# Domino_Qi.net
KiCad netlist of a schematic drawn in EAGLE
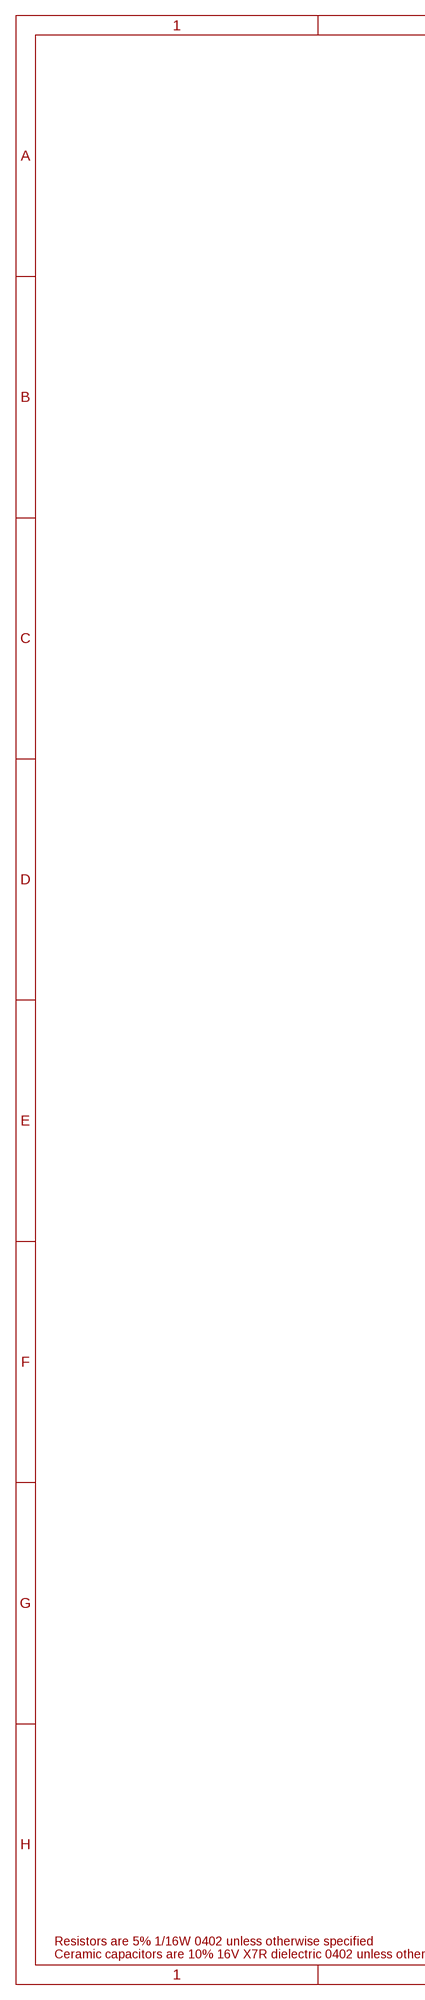
[diagram p0: schematic, sheet 1, part 1 of 2]
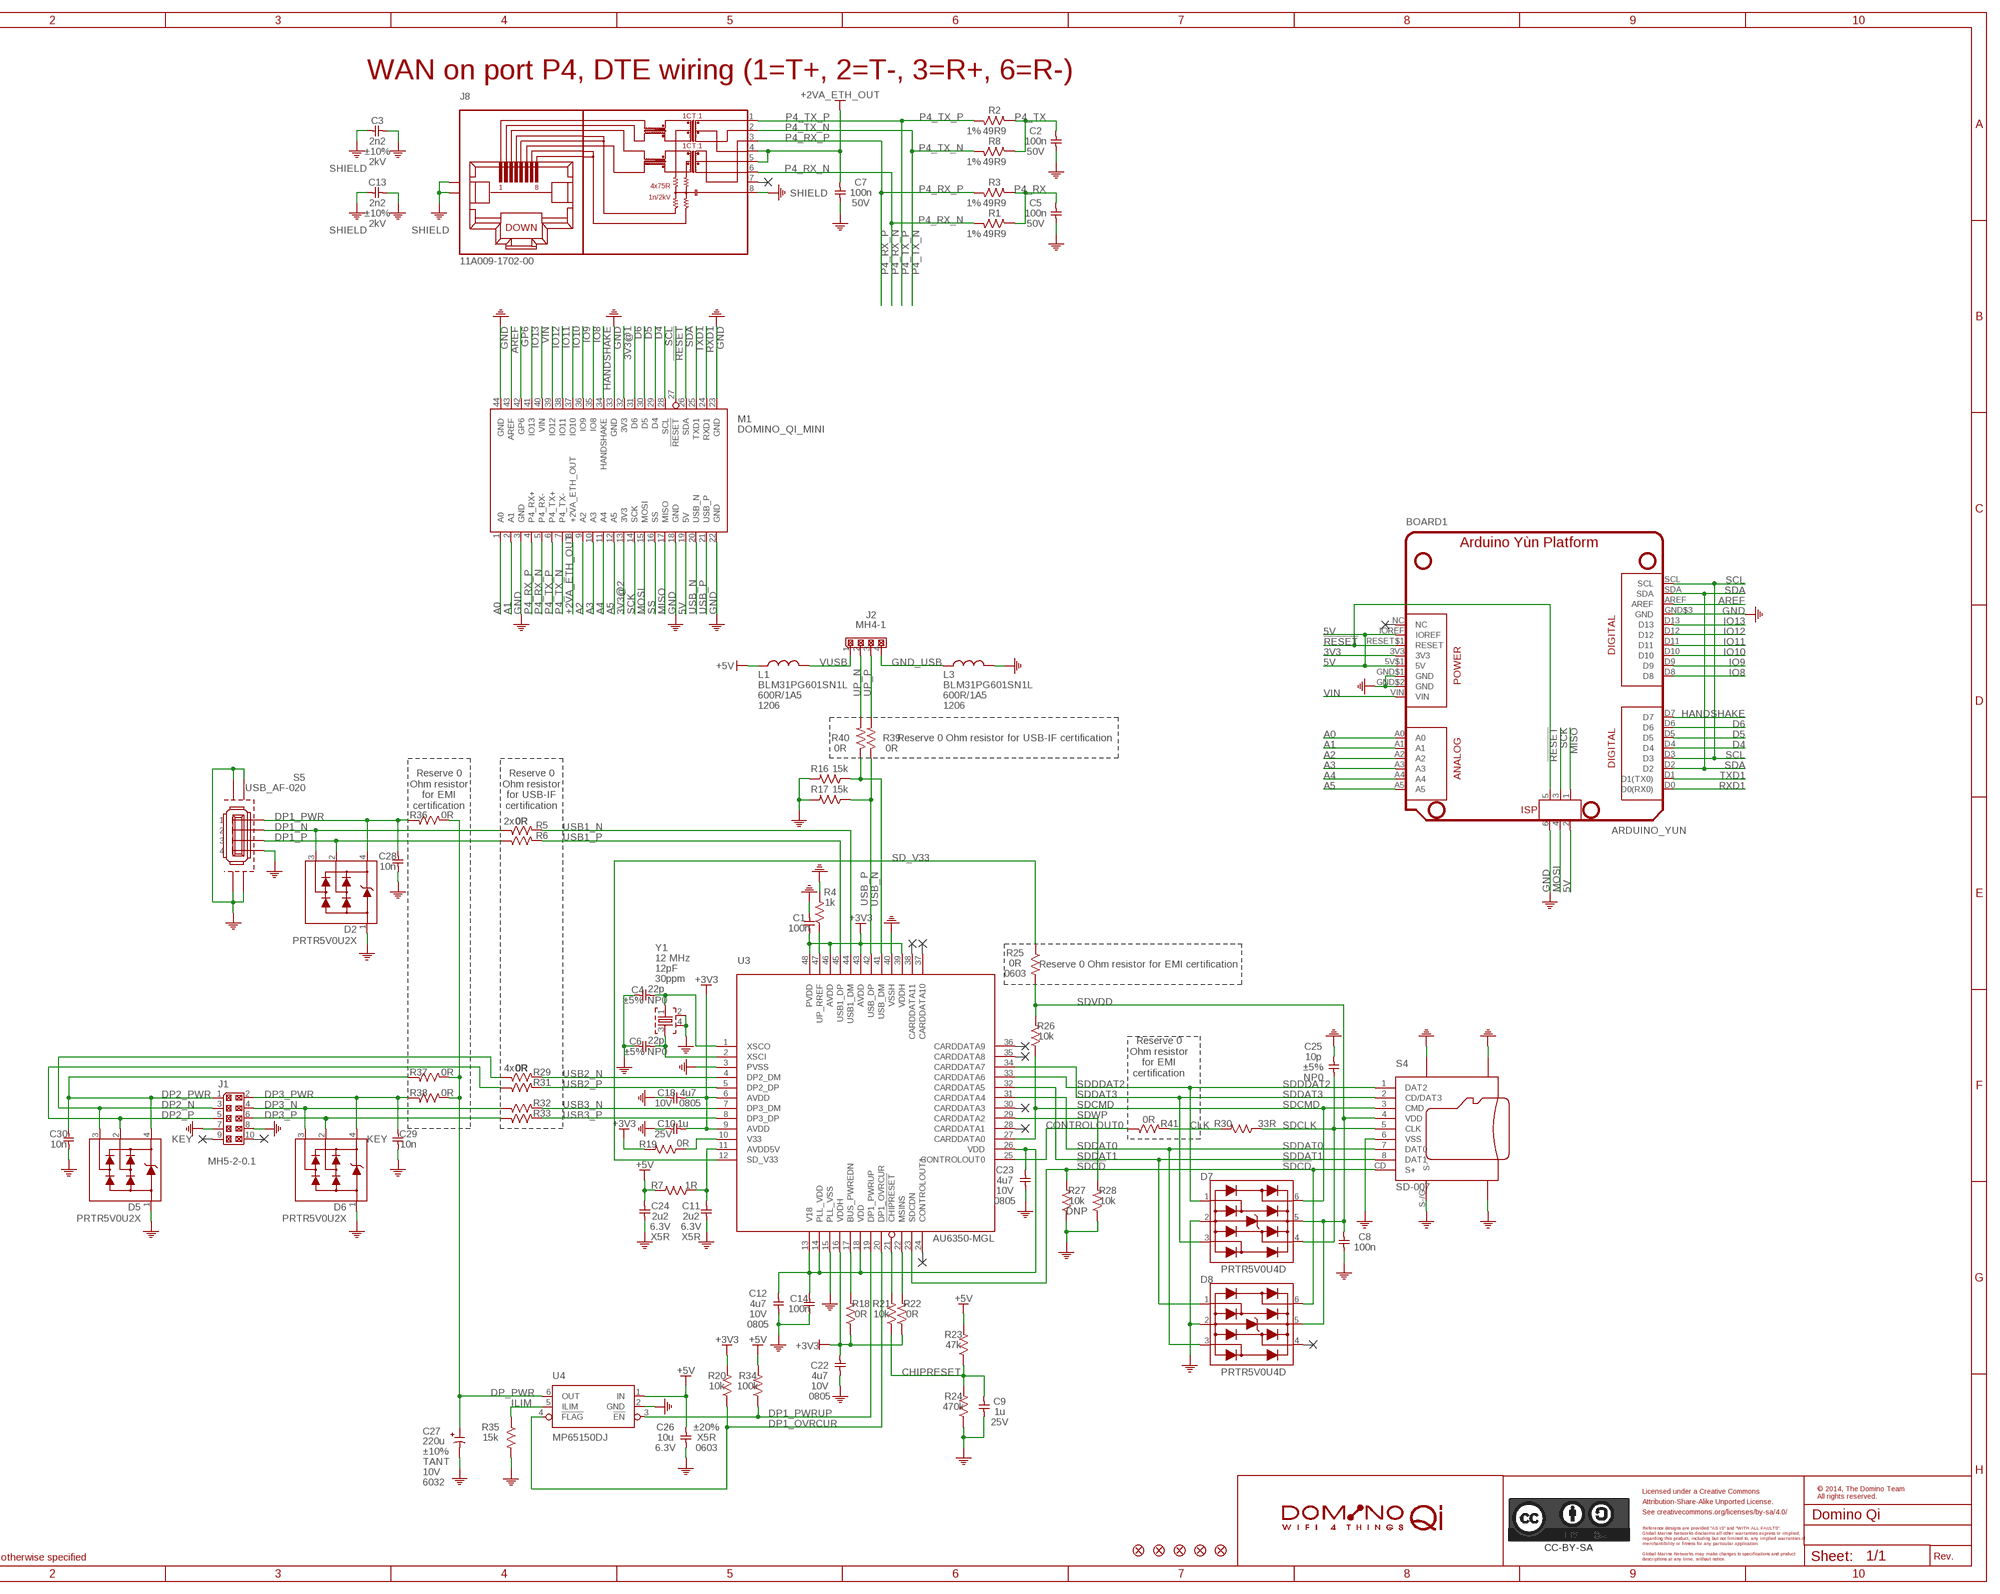
[diagram p1: schematic, sheet 1, part 2 of 2]

(export (version "E")
  (design (tool "Eeschema 10.0.6"))
  (components
    (comp (ref "BOARD1")
      (value "ARDUINO_YUN")
      (footprint "eagle-import:ARDUINO-YUN-PLATFORM")
      (libsource (lib "eagle-import") (part "ARDUINO_YUN"))
    )
    (comp (ref "C1")
      (value "100n")
      (footprint "eagle-import:C0402")
      (fields (field (name "PARTNO") "C0402_100n_X7R_10%_CER_50V"))
      (libsource (lib "eagle-import") (part "CAP_0402"))
    )
    (comp (ref "C2")
      (value "100n")
      (footprint "eagle-import:C0402")
      (fields (field (name "PARTNO") "C0402_100n_X7R_10%_CER_50V") (field (name "VOLT") "50V"))
      (libsource (lib "eagle-import") (part "CAP_0402"))
    )
    (comp (ref "C3")
      (value "2n2")
      (footprint "eagle-import:C1206")
      (fields
        (field (name "PARTNO") "C1210_2n2_X7R_10%_CER_2kV")
        (field (name "TOL") "±10%")
        (field (name "VOLT") "2kV")
      )
      (libsource (lib "eagle-import") (part "CAP_1206"))
    )
    (comp (ref "C4")
      (value "22p")
      (footprint "eagle-import:C0402")
      (fields
        (field (name "PARTNO") "C0402_22p_NP0_5%_CER_50V")
        (field (name "TC") "NP0")
        (field (name "TOL") "±5%")
      )
      (libsource (lib "eagle-import") (part "CAP_0402"))
    )
    (comp (ref "C5")
      (value "100n")
      (footprint "eagle-import:C0402")
      (fields (field (name "PARTNO") "C0402_100n_X7R_10%_CER_50V") (field (name "VOLT") "50V"))
      (libsource (lib "eagle-import") (part "CAP_0402"))
    )
    (comp (ref "C6")
      (value "22p")
      (footprint "eagle-import:C0402")
      (fields
        (field (name "PARTNO") "C0402_22p_NP0_5%_CER_50V")
        (field (name "TC") "NP0")
        (field (name "TOL") "±5%")
      )
      (libsource (lib "eagle-import") (part "CAP_0402"))
    )
    (comp (ref "C7")
      (value "100n")
      (footprint "eagle-import:C0402")
      (fields (field (name "PARTNO") "C0402_100n_X7R_10%_CER_50V") (field (name "VOLT") "50V"))
      (libsource (lib "eagle-import") (part "CAP_0402"))
    )
    (comp (ref "C8")
      (value "100n")
      (footprint "eagle-import:C0402")
      (fields (field (name "PARTNO") "C0402_100n_X7R_10%_CER_50V"))
      (libsource (lib "eagle-import") (part "CAP_0402"))
    )
    (comp (ref "C9")
      (value "1u")
      (footprint "eagle-import:C0402")
      (fields (field (name "PARTNO") "C0402_1u_X7R_10%_CER_25V") (field (name "VOLT") "25V"))
      (libsource (lib "eagle-import") (part "CAP_0402"))
    )
    (comp (ref "C10")
      (value "1u")
      (footprint "eagle-import:C0402")
      (fields (field (name "PARTNO") "C0402_1u_X7R_10%_CER_25V") (field (name "VOLT") "25V"))
      (libsource (lib "eagle-import") (part "CAP_0402"))
    )
    (comp (ref "C11")
      (value "2u2")
      (footprint "eagle-import:C0402")
      (fields
        (field (name "PARTNO") "C0402_2u2_X5R_10%_CER_6V3")
        (field (name "TC") "X5R")
        (field (name "VOLT") "6.3V")
      )
      (libsource (lib "eagle-import") (part "CAP_0402"))
    )
    (comp (ref "C12")
      (value "4u7")
      (footprint "eagle-import:C0805")
      (fields
        (field (name "SIZE") "0805")
        (field (name "PARTNO") "C0805_4u7_X7R_10%_CER_6V3")
        (field (name "VOLT") "10V")
      )
      (libsource (lib "eagle-import") (part "CAP_0805"))
    )
    (comp (ref "C13")
      (value "2n2")
      (footprint "eagle-import:C1206")
      (fields
        (field (name "PARTNO") "C1210_2n2_X7R_10%_CER_2kV")
        (field (name "TOL") "±10%")
        (field (name "VOLT") "2kV")
      )
      (libsource (lib "eagle-import") (part "CAP_1206"))
    )
    (comp (ref "C14")
      (value "100n")
      (footprint "eagle-import:C0402")
      (fields (field (name "PARTNO") "C0402_100n_X7R_10%_CER_50V"))
      (libsource (lib "eagle-import") (part "CAP_0402"))
    )
    (comp (ref "C18")
      (value "4u7")
      (footprint "eagle-import:C0805")
      (fields
        (field (name "SIZE") "0805")
        (field (name "PARTNO") "C0805_4u7_X7R_10%_CER_6V3")
        (field (name "VOLT") "10V")
      )
      (libsource (lib "eagle-import") (part "CAP_0805"))
    )
    (comp (ref "C22")
      (value "4u7")
      (footprint "eagle-import:C0805")
      (fields
        (field (name "SIZE") "0805")
        (field (name "PARTNO") "C0805_4u7_X7R_10%_CER_6V3")
        (field (name "VOLT") "10V")
      )
      (libsource (lib "eagle-import") (part "CAP_0805"))
    )
    (comp (ref "C23")
      (value "4u7")
      (footprint "eagle-import:C0805")
      (fields
        (field (name "SIZE") "0805")
        (field (name "PARTNO") "C0805_4u7_X7R_10%_CER_6V3")
        (field (name "VOLT") "10V")
      )
      (libsource (lib "eagle-import") (part "CAP_0805"))
    )
    (comp (ref "C24")
      (value "2u2")
      (footprint "eagle-import:C0402")
      (fields
        (field (name "PARTNO") "C0402_2u2_X5R_10%_CER_6V3")
        (field (name "TC") "X5R")
        (field (name "VOLT") "6.3V")
      )
      (libsource (lib "eagle-import") (part "CAP_0402"))
    )
    (comp (ref "C25")
      (value "10p")
      (footprint "eagle-import:C0402")
      (fields
        (field (name "PARTNO") "C0402_10p_NP0_5%_CER_50V")
        (field (name "TC") "NP0")
        (field (name "TOL") "±5%")
      )
      (libsource (lib "eagle-import") (part "CAP_0402"))
    )
    (comp (ref "C26")
      (value "10u")
      (footprint "eagle-import:C0603")
      (fields
        (field (name "SIZE") "0603")
        (field (name "PARTNO") "C0603_10u_X5R_20%_CER_6V3")
        (field (name "TC") "X5R")
        (field (name "TOL") "±20%")
        (field (name "VOLT") "6.3V")
      )
      (libsource (lib "eagle-import") (part "CAP_0603"))
    )
    (comp (ref "C27")
      (value "220u")
      (footprint "eagle-import:C_6032-25")
      (fields
        (field (name "SIZE") "6032")
        (field (name "TYPE") "TANT")
        (field (name "PARTNO") "CPOLC-6032_220u_20%_TANT_10V")
        (field (name "TOL") "±10%")
        (field (name "VOLT") "10V")
      )
      (libsource (lib "eagle-import") (part "CPOL_?C/6032-25"))
    )
    (comp (ref "C28")
      (value "10n")
      (footprint "eagle-import:C0402")
      (fields (field (name "PARTNO") "C0402_10n_X7R_10%_CER_50V"))
      (libsource (lib "eagle-import") (part "CAP_0402"))
    )
    (comp (ref "C29")
      (value "10n")
      (footprint "eagle-import:C0402")
      (fields (field (name "PARTNO") "C0402_10n_X7R_10%_CER_50V"))
      (libsource (lib "eagle-import") (part "CAP_0402"))
    )
    (comp (ref "C30")
      (value "10n")
      (footprint "eagle-import:C0402")
      (fields (field (name "PARTNO") "C0402_10n_X7R_10%_CER_50V"))
      (libsource (lib "eagle-import") (part "CAP_0402"))
    )
    (comp (ref "D2")
      (value "PRTR5V0U2X")
      (footprint "eagle-import:SOT143B")
      (libsource (lib "eagle-import") (part "PRTR5V0U2X"))
    )
    (comp (ref "D5")
      (value "PRTR5V0U2X")
      (footprint "eagle-import:SOT143B")
      (libsource (lib "eagle-import") (part "PRTR5V0U2X"))
    )
    (comp (ref "D6")
      (value "PRTR5V0U2X")
      (footprint "eagle-import:SOT143B")
      (libsource (lib "eagle-import") (part "PRTR5V0U2X"))
    )
    (comp (ref "D7")
      (value "PRTR5V0U4D")
      (footprint "eagle-import:SOT23-6")
      (libsource (lib "eagle-import") (part "PRTR5V0U4D"))
    )
    (comp (ref "D8")
      (value "PRTR5V0U4D")
      (footprint "eagle-import:SOT23-6")
      (libsource (lib "eagle-import") (part "PRTR5V0U4D"))
    )
    (comp (ref "F1")
      (value "FIDUCIAL")
      (footprint "eagle-import:FIDUCIAL")
      (libsource (lib "eagle-import") (part "FIDUCIAL"))
    )
    (comp (ref "F2")
      (value "FIDUCIAL")
      (footprint "eagle-import:FIDUCIAL")
      (libsource (lib "eagle-import") (part "FIDUCIAL"))
    )
    (comp (ref "F4")
      (value "FIDUCIAL")
      (footprint "eagle-import:FIDUCIAL")
      (libsource (lib "eagle-import") (part "FIDUCIAL"))
    )
    (comp (ref "F5")
      (value "FIDUCIAL")
      (footprint "eagle-import:FIDUCIAL")
      (libsource (lib "eagle-import") (part "FIDUCIAL"))
    )
    (comp (ref "F6")
      (value "FIDUCIAL")
      (footprint "eagle-import:FIDUCIAL")
      (libsource (lib "eagle-import") (part "FIDUCIAL"))
    )
    (comp (ref "J1")
      (value "MH5-2-0.1")
      (footprint "eagle-import:MH05-2-0.1")
      (libsource (lib "eagle-import") (part "MH5-2"))
    )
    (comp (ref "J2")
      (value "MH4-1")
      (footprint "eagle-import:MH4-1-0.1")
      (fields (field (name "PARTNO") "MH4-1-0.1"))
      (libsource (lib "eagle-import") (part "MH4-1"))
    )
    (comp (ref "J8")
      (value "11A009-1702-00")
      (footprint "eagle-import:11A009-1702-00")
      (libsource (lib "eagle-import") (part "11A009-1702-00"))
    )
    (comp (ref "L1")
      (value "BLM31PG601SN1L")
      (footprint "eagle-import:FB1206")
      (fields (field (name "SIZE") "1206") (field (name "OPT") "600R/1A5"))
      (libsource (lib "eagle-import") (part "FB_1206"))
    )
    (comp (ref "L3")
      (value "BLM31PG601SN1L")
      (footprint "eagle-import:FB1206")
      (fields (field (name "SIZE") "1206") (field (name "OPT") "600R/1A5"))
      (libsource (lib "eagle-import") (part "FB_1206"))
    )
    (comp (ref "M1")
      (value "DOMINO_QI_MINI")
      (footprint "eagle-import:DOMINO_QI_MINI")
      (libsource (lib "eagle-import") (part "DOMINO_QI_MINI"))
    )
    (comp (ref "R1")
      (value "49R9")
      (footprint "eagle-import:R0402")
      (fields (field (name "PARTNO") "R0402_49R9_1%_62.5mW") (field (name "TOL") "1%"))
      (libsource (lib "eagle-import") (part "RES_0402"))
    )
    (comp (ref "R2")
      (value "49R9")
      (footprint "eagle-import:R0402")
      (fields (field (name "PARTNO") "R0402_49R9_1%_62.5mW") (field (name "TOL") "1%"))
      (libsource (lib "eagle-import") (part "RES_0402"))
    )
    (comp (ref "R3")
      (value "49R9")
      (footprint "eagle-import:R0402")
      (fields (field (name "PARTNO") "R0402_49R9_1%_62.5mW") (field (name "TOL") "1%"))
      (libsource (lib "eagle-import") (part "RES_0402"))
    )
    (comp (ref "R4")
      (value "1k")
      (footprint "eagle-import:R0402")
      (fields (field (name "PARTNO") "R0402_1k_5%_62.5mW"))
      (libsource (lib "eagle-import") (part "RES_0402"))
    )
    (comp (ref "R5")
      (value "0R")
      (footprint "eagle-import:R0402")
      (fields (field (name "PARTNO") "R0402_0R_5%_62.5mW"))
      (libsource (lib "eagle-import") (part "RES_0402"))
    )
    (comp (ref "R6")
      (value "0R")
      (footprint "eagle-import:R0402")
      (fields (field (name "PARTNO") "R0402_0R_5%_62.5mW"))
      (libsource (lib "eagle-import") (part "RES_0402"))
    )
    (comp (ref "R7")
      (value "1R")
      (footprint "eagle-import:R0402")
      (fields (field (name "PARTNO") "R0402_1R_5%_62.5mW"))
      (libsource (lib "eagle-import") (part "RES_0402"))
    )
    (comp (ref "R8")
      (value "49R9")
      (footprint "eagle-import:R0402")
      (fields (field (name "PARTNO") "R0402_49R9_1%_62.5mW") (field (name "TOL") "1%"))
      (libsource (lib "eagle-import") (part "RES_0402"))
    )
    (comp (ref "R16")
      (value "15k")
      (footprint "eagle-import:R0402")
      (fields (field (name "PARTNO") "R0402_15k_5%_62.5mW"))
      (libsource (lib "eagle-import") (part "RES_0402"))
    )
    (comp (ref "R17")
      (value "15k")
      (footprint "eagle-import:R0402")
      (fields (field (name "PARTNO") "R0402_15k_5%_62.5mW"))
      (libsource (lib "eagle-import") (part "RES_0402"))
    )
    (comp (ref "R18")
      (value "0R")
      (footprint "eagle-import:R0402")
      (fields (field (name "PARTNO") "R0402_0R_5%_62.5mW"))
      (libsource (lib "eagle-import") (part "RES_0402"))
    )
    (comp (ref "R19")
      (value "0R")
      (footprint "eagle-import:R0402")
      (fields (field (name "PARTNO") "R0402_0R_5%_62.5mW"))
      (libsource (lib "eagle-import") (part "RES_0402"))
    )
    (comp (ref "R20")
      (value "10k")
      (footprint "eagle-import:R0402")
      (fields (field (name "PARTNO") "R0402_10k_5%_62.5mW"))
      (libsource (lib "eagle-import") (part "RES_0402"))
    )
    (comp (ref "R21")
      (value "10k")
      (footprint "eagle-import:R0402")
      (fields (field (name "PARTNO") "R0402_10k_5%_62.5mW"))
      (libsource (lib "eagle-import") (part "RES_0402"))
    )
    (comp (ref "R22")
      (value "0R")
      (footprint "eagle-import:R0402")
      (fields (field (name "PARTNO") "R0402_0R_5%_62.5mW"))
      (libsource (lib "eagle-import") (part "RES_0402"))
    )
    (comp (ref "R23")
      (value "47k")
      (footprint "eagle-import:R0402")
      (fields (field (name "PARTNO") "R0402_47k_5%_62.5mW"))
      (libsource (lib "eagle-import") (part "RES_0402"))
    )
    (comp (ref "R24")
      (value "470k")
      (footprint "eagle-import:R0402")
      (fields (field (name "PARTNO") "R0402_470k_5%_62.5mW"))
      (libsource (lib "eagle-import") (part "RES_0402"))
    )
    (comp (ref "R25")
      (value "0R")
      (footprint "eagle-import:R0603")
      (fields (field (name "SIZE") "0603") (field (name "PARTNO") "R0603_0R_5%_125mW"))
      (libsource (lib "eagle-import") (part "RES_0603"))
    )
    (comp (ref "R26")
      (value "10k")
      (footprint "eagle-import:R0402")
      (fields (field (name "PARTNO") "R0402_10k_5%_62.5mW"))
      (libsource (lib "eagle-import") (part "RES_0402"))
    )
    (comp (ref "R27")
      (value "10k")
      (footprint "eagle-import:R0402")
      (fields (field (name "PARTNO") "R0402_10k_5%_62.5mW"))
      (libsource (lib "eagle-import") (part "RES_0402"))
    )
    (comp (ref "R28")
      (value "10k")
      (footprint "eagle-import:R0402")
      (fields (field (name "PARTNO") "R0402_10k_5%_62.5mW"))
      (libsource (lib "eagle-import") (part "RES_0402"))
    )
    (comp (ref "R29")
      (value "0R")
      (footprint "eagle-import:R0402")
      (fields (field (name "PARTNO") "R0402_0R_5%_62.5mW"))
      (libsource (lib "eagle-import") (part "RES_0402"))
    )
    (comp (ref "R30")
      (value "33R")
      (footprint "eagle-import:R0402")
      (fields (field (name "PARTNO") "R0402_33R_5%_62.5mW"))
      (libsource (lib "eagle-import") (part "RES_0402"))
    )
    (comp (ref "R31")
      (value "0R")
      (footprint "eagle-import:R0402")
      (fields (field (name "PARTNO") "R0402_0R_5%_62.5mW"))
      (libsource (lib "eagle-import") (part "RES_0402"))
    )
    (comp (ref "R32")
      (value "0R")
      (footprint "eagle-import:R0402")
      (fields (field (name "PARTNO") "R0402_0R_5%_62.5mW"))
      (libsource (lib "eagle-import") (part "RES_0402"))
    )
    (comp (ref "R33")
      (value "0R")
      (footprint "eagle-import:R0402")
      (fields (field (name "PARTNO") "R0402_0R_5%_62.5mW"))
      (libsource (lib "eagle-import") (part "RES_0402"))
    )
    (comp (ref "R34")
      (value "100k")
      (footprint "eagle-import:R0402")
      (fields (field (name "PARTNO") "R0402_100k_5%_62.5mW"))
      (libsource (lib "eagle-import") (part "RES_0402"))
    )
    (comp (ref "R35")
      (value "15k")
      (footprint "eagle-import:R0402")
      (fields (field (name "PARTNO") "R0402_15k_5%_62.5mW"))
      (libsource (lib "eagle-import") (part "RES_0402"))
    )
    (comp (ref "R36")
      (value "0R")
      (footprint "eagle-import:R0402")
      (fields (field (name "PARTNO") "R0402_0R_5%_62.5mW"))
      (libsource (lib "eagle-import") (part "RES_0402"))
    )
    (comp (ref "R37")
      (value "0R")
      (footprint "eagle-import:R0402")
      (fields (field (name "PARTNO") "R0402_0R_5%_62.5mW"))
      (libsource (lib "eagle-import") (part "RES_0402"))
    )
    (comp (ref "R38")
      (value "0R")
      (footprint "eagle-import:R0402")
      (fields (field (name "PARTNO") "R0402_0R_5%_62.5mW"))
      (libsource (lib "eagle-import") (part "RES_0402"))
    )
    (comp (ref "R39")
      (value "0R")
      (footprint "eagle-import:R0402")
      (fields (field (name "PARTNO") "R0402_0R_5%_62.5mW"))
      (libsource (lib "eagle-import") (part "RES_0402"))
    )
    (comp (ref "R40")
      (value "0R")
      (footprint "eagle-import:R0402")
      (fields (field (name "PARTNO") "R0402_0R_5%_62.5mW"))
      (libsource (lib "eagle-import") (part "RES_0402"))
    )
    (comp (ref "R41")
      (value "0R")
      (footprint "eagle-import:R0402")
      (fields (field (name "PARTNO") "R0402_0R_5%_62.5mW"))
      (libsource (lib "eagle-import") (part "RES_0402"))
    )
    (comp (ref "S4")
      (value "SD-007")
      (footprint "eagle-import:SD-007")
      (libsource (lib "eagle-import") (part "MICRO-SD"))
    )
    (comp (ref "S5")
      (value "USB_AF-020")
      (footprint "eagle-import:USB_AF-020")
      (libsource (lib "eagle-import") (part "USB_AF-020"))
    )
    (comp (ref "U$2")
      (value "CC-BY-SA_LOGO")
      (footprint "eagle-import:CC-BY-SA_LOGO")
      (libsource (lib "eagle-import") (part "CC-BY-SA_LOGO"))
    )
    (comp (ref "U$13")
      (value "DOMINO_QI_LOGO")
      (footprint "eagle-import:DOMINO_QI_LOGO")
      (libsource (lib "eagle-import") (part "DOMINO_QI_LOGO"))
    )
    (comp (ref "U3")
      (value "AU6350-MGL")
      (footprint "eagle-import:LQFP-48_7X7")
      (libsource (lib "eagle-import") (part "AU6350-MGL"))
    )
    (comp (ref "U4")
      (value "MP65150DJ")
      (footprint "eagle-import:SOT23-6")
      (libsource (lib "eagle-import") (part "MP65150DJ"))
    )
    (comp (ref "Y1")
      (value "12 MHz")
      (footprint "eagle-import:CRYSTAL_32X25")
      (fields
        (field (name "LOAD") "12pF")
        (field (name "PARTNO") "CRYSTAL_32X25_2SH_12PF_30PPM")
        (field (name "TOL") "30ppm")
      )
      (libsource (lib "eagle-import") (part "CRYSTAL_2SH"))
    )
  )
  (nets
    (net (code "1") (name "+2VA_ETH_OUT") (class "Default")
      (node (ref "C7") (pin "2") (pinfunction "2_2") (pintype "passive"))
      (node (ref "J8") (pin "4") (pinfunction "P4_4") (pintype "passive"))
      (node (ref "J8") (pin "5") (pinfunction "P5_5") (pintype "passive"))
      (node (ref "M1") (pin "8") (pinfunction "+2VA_ETH_OUT_8") (pintype "power_in"))
    )
    (net (code "2") (name "+3V3") (class "Default")
      (node (ref "C1") (pin "2") (pinfunction "2_2") (pintype "passive"))
      (node (ref "C10") (pin "2") (pinfunction "2_2") (pintype "passive"))
      (node (ref "C18") (pin "2") (pinfunction "2_2") (pintype "passive"))
      (node (ref "C22") (pin "2") (pinfunction "2_2") (pintype "passive"))
      (node (ref "R18") (pin "1") (pinfunction "1_1") (pintype "passive"))
      (node (ref "R19") (pin "2") (pinfunction "2_2") (pintype "passive"))
      (node (ref "R20") (pin "2") (pinfunction "2_2") (pintype "passive"))
      (node (ref "R22") (pin "1") (pinfunction "1_1") (pintype "passive"))
      (node (ref "U3") (pin "16") (pinfunction "VDDH_16") (pintype "power_in"))
      (node (ref "U3") (pin "39") (pinfunction "VDDH_39") (pintype "power_in"))
      (node (ref "U3") (pin "43") (pinfunction "AVDD_43") (pintype "power_in"))
      (node (ref "U3") (pin "46") (pinfunction "AVDD_46") (pintype "power_in"))
      (node (ref "U3") (pin "48") (pinfunction "PVDD_48") (pintype "power_in"))
      (node (ref "U3") (pin "6") (pinfunction "AVDD_6") (pintype "power_in"))
      (node (ref "U3") (pin "9") (pinfunction "AVDD_9") (pintype "power_in"))
    )
    (net (code "3") (name "+5V") (class "Default")
      (node (ref "C24") (pin "1") (pinfunction "1_1") (pintype "passive"))
      (node (ref "C26") (pin "1") (pinfunction "1_1") (pintype "passive"))
      (node (ref "L1") (pin "2") (pinfunction "2_2") (pintype "passive"))
      (node (ref "R23") (pin "2") (pinfunction "2_2") (pintype "passive"))
      (node (ref "R34") (pin "2") (pinfunction "2_2") (pintype "passive"))
      (node (ref "R7") (pin "2") (pinfunction "2_2") (pintype "passive"))
      (node (ref "U4") (pin "1") (pinfunction "IN_1") (pintype "power_in"))
    )
    (net (code "4") (name "/3V3") (class "Default")
      (node (ref "BOARD1") (pin "3V3") (pinfunction "3V3_3V3") (pintype "power_in"))
    )
    (net (code "5") (name "/3V3@1") (class "Default")
      (node (ref "M1") (pin "32") (pinfunction "3V3_32") (pintype "power_in"))
    )
    (net (code "6") (name "/3V3@2") (class "Default")
      (node (ref "M1") (pin "13") (pinfunction "3V3_13") (pintype "power_in"))
    )
    (net (code "7") (name "/5V") (class "Default")
      (node (ref "BOARD1") (pin "2") (pinfunction "5V_2") (pintype "power_in"))
      (node (ref "BOARD1") (pin "5V$1") (pinfunction "5V_5V$1") (pintype "power_in"))
      (node (ref "BOARD1") (pin "IOREF") (pinfunction "IOREF_IOREF") (pintype "power_in"))
      (node (ref "M1") (pin "19") (pinfunction "5V_19") (pintype "power_in"))
    )
    (net (code "8") (name "/A0") (class "Default")
      (node (ref "BOARD1") (pin "A0") (pinfunction "A0_A0") (pintype "bidirectional"))
      (node (ref "M1") (pin "1") (pinfunction "A0_1") (pintype "bidirectional"))
    )
    (net (code "9") (name "/A1") (class "Default")
      (node (ref "BOARD1") (pin "A1") (pinfunction "A1_A1") (pintype "bidirectional"))
      (node (ref "M1") (pin "2") (pinfunction "A1_2") (pintype "bidirectional"))
    )
    (net (code "10") (name "/A2") (class "Default")
      (node (ref "BOARD1") (pin "A2") (pinfunction "A2_A2") (pintype "bidirectional"))
      (node (ref "M1") (pin "9") (pinfunction "A2_9") (pintype "bidirectional"))
    )
    (net (code "11") (name "/A3") (class "Default")
      (node (ref "BOARD1") (pin "A3") (pinfunction "A3_A3") (pintype "bidirectional"))
      (node (ref "M1") (pin "10") (pinfunction "A3_10") (pintype "bidirectional"))
    )
    (net (code "12") (name "/A4") (class "Default")
      (node (ref "BOARD1") (pin "A4") (pinfunction "A4_A4") (pintype "bidirectional"))
      (node (ref "M1") (pin "11") (pinfunction "A4_11") (pintype "bidirectional"))
    )
    (net (code "13") (name "/A5") (class "Default")
      (node (ref "BOARD1") (pin "A5") (pinfunction "A5_A5") (pintype "bidirectional"))
      (node (ref "M1") (pin "12") (pinfunction "A5_12") (pintype "bidirectional"))
    )
    (net (code "14") (name "/AREF") (class "Default")
      (node (ref "BOARD1") (pin "AREF") (pinfunction "AREF_AREF") (pintype "passive"))
      (node (ref "M1") (pin "43") (pinfunction "AREF_43") (pintype "passive"))
    )
    (net (code "15") (name "/CHIPRESET") (class "Default")
      (node (ref "C9") (pin "1") (pinfunction "1_1") (pintype "passive"))
      (node (ref "R21") (pin "1") (pinfunction "1_1") (pintype "passive"))
      (node (ref "R23") (pin "1") (pinfunction "1_1") (pintype "passive"))
      (node (ref "R24") (pin "2") (pinfunction "2_2") (pintype "passive"))
    )
    (net (code "16") (name "/CLK") (class "Default")
      (node (ref "R30") (pin "2") (pinfunction "2_2") (pintype "passive"))
      (node (ref "R41") (pin "2") (pinfunction "2_2") (pintype "passive"))
    )
    (net (code "17") (name "/CONTROLOUT0") (class "Default")
      (node (ref "R41") (pin "1") (pinfunction "1_1") (pintype "passive"))
      (node (ref "U3") (pin "25") (pinfunction "CONTROLOUT0_25") (pintype "output"))
    )
    (net (code "18") (name "/D4") (class "Default")
      (node (ref "BOARD1") (pin "D4") (pinfunction "D4_D4") (pintype "bidirectional"))
      (node (ref "M1") (pin "29") (pinfunction "D4_29") (pintype "bidirectional"))
    )
    (net (code "19") (name "/D5") (class "Default")
      (node (ref "BOARD1") (pin "D5") (pinfunction "D5_D5") (pintype "bidirectional"))
      (node (ref "M1") (pin "30") (pinfunction "D5_30") (pintype "bidirectional"))
    )
    (net (code "20") (name "/D6") (class "Default")
      (node (ref "BOARD1") (pin "D6") (pinfunction "D6_D6") (pintype "bidirectional"))
      (node (ref "M1") (pin "31") (pinfunction "D6_31") (pintype "bidirectional"))
    )
    (net (code "21") (name "/DP1_N") (class "Default")
      (node (ref "D2") (pin "3") (pinfunction "P$3_3") (pintype "passive"))
      (node (ref "R5") (pin "1") (pinfunction "1_1") (pintype "passive"))
      (node (ref "S5") (pin "2") (pinfunction "2_2") (pintype "passive"))
    )
    (net (code "22") (name "/DP1_OVRCUR") (class "Default")
      (node (ref "R20") (pin "1") (pinfunction "1_1") (pintype "passive"))
      (node (ref "U3") (pin "20") (pinfunction "DP1_OVRCUR_20") (pintype "input"))
      (node (ref "U4") (pin "4") (pinfunction "~{FLAG}_4") (pintype "open_collector"))
    )
    (net (code "23") (name "/DP1_P") (class "Default")
      (node (ref "D2") (pin "2") (pinfunction "P$2_2") (pintype "passive"))
      (node (ref "R6") (pin "1") (pinfunction "1_1") (pintype "passive"))
      (node (ref "S5") (pin "3") (pinfunction "3_3") (pintype "passive"))
    )
    (net (code "24") (name "/DP1_PWR") (class "Default")
      (node (ref "C28") (pin "1") (pinfunction "1_1") (pintype "passive"))
      (node (ref "D2") (pin "4") (pinfunction "P$4_4") (pintype "passive"))
      (node (ref "R36") (pin "1") (pinfunction "1_1") (pintype "passive"))
      (node (ref "S5") (pin "1") (pinfunction "1_1") (pintype "passive"))
    )
    (net (code "25") (name "/DP1_PWRUP") (class "Default")
      (node (ref "R34") (pin "1") (pinfunction "1_1") (pintype "passive"))
      (node (ref "U3") (pin "19") (pinfunction "DP1_PWRUP_19") (pintype "output"))
      (node (ref "U4") (pin "3") (pinfunction "~{EN}_3") (pintype "input"))
    )
    (net (code "26") (name "/DP2_N") (class "Default")
      (node (ref "D5") (pin "3") (pinfunction "P$3_3") (pintype "passive"))
      (node (ref "J1") (pin "3") (pinfunction "3_3") (pintype "passive"))
      (node (ref "R29") (pin "1") (pinfunction "1_1") (pintype "passive"))
    )
    (net (code "27") (name "/DP2_P") (class "Default")
      (node (ref "D5") (pin "2") (pinfunction "P$2_2") (pintype "passive"))
      (node (ref "J1") (pin "5") (pinfunction "5_5") (pintype "passive"))
      (node (ref "R31") (pin "1") (pinfunction "1_1") (pintype "passive"))
    )
    (net (code "28") (name "/DP2_PWR") (class "Default")
      (node (ref "C30") (pin "1") (pinfunction "1_1") (pintype "passive"))
      (node (ref "D5") (pin "4") (pinfunction "P$4_4") (pintype "passive"))
      (node (ref "J1") (pin "1") (pinfunction "1_1") (pintype "passive"))
      (node (ref "R37") (pin "1") (pinfunction "1_1") (pintype "passive"))
    )
    (net (code "29") (name "/DP3_N") (class "Default")
      (node (ref "D6") (pin "3") (pinfunction "P$3_3") (pintype "passive"))
      (node (ref "J1") (pin "4") (pinfunction "4_4") (pintype "passive"))
      (node (ref "R32") (pin "1") (pinfunction "1_1") (pintype "passive"))
    )
    (net (code "30") (name "/DP3_P") (class "Default")
      (node (ref "D6") (pin "2") (pinfunction "P$2_2") (pintype "passive"))
      (node (ref "J1") (pin "6") (pinfunction "6_6") (pintype "passive"))
      (node (ref "R33") (pin "1") (pinfunction "1_1") (pintype "passive"))
    )
    (net (code "31") (name "/DP3_PWR") (class "Default")
      (node (ref "C29") (pin "1") (pinfunction "1_1") (pintype "passive"))
      (node (ref "D6") (pin "4") (pinfunction "P$4_4") (pintype "passive"))
      (node (ref "J1") (pin "2") (pinfunction "2_2") (pintype "passive"))
      (node (ref "R38") (pin "1") (pinfunction "1_1") (pintype "passive"))
    )
    (net (code "32") (name "/DP_PWR") (class "Default")
      (node (ref "C27") (pin "1") (pinfunction "+_1") (pintype "passive"))
      (node (ref "R36") (pin "2") (pinfunction "2_2") (pintype "passive"))
      (node (ref "R37") (pin "2") (pinfunction "2_2") (pintype "passive"))
      (node (ref "R38") (pin "2") (pinfunction "2_2") (pintype "passive"))
      (node (ref "U4") (pin "6") (pinfunction "OUT_6") (pintype "power_in"))
    )
    (net (code "33") (name "/GND_USB") (class "Default")
      (node (ref "J2") (pin "4") (pinfunction "4_4") (pintype "passive"))
      (node (ref "L3") (pin "2") (pinfunction "2_2") (pintype "passive"))
    )
    (net (code "34") (name "/GP6") (class "Default")
      (node (ref "M1") (pin "42") (pinfunction "GP6_42") (pintype "bidirectional"))
    )
    (net (code "35") (name "/HANDSHAKE") (class "Default")
      (node (ref "BOARD1") (pin "D7") (pinfunction "D7_D7") (pintype "bidirectional"))
      (node (ref "M1") (pin "34") (pinfunction "HANDSHAKE_34") (pintype "bidirectional"))
    )
    (net (code "36") (name "/ILIM") (class "Default")
      (node (ref "R35") (pin "1") (pinfunction "1_1") (pintype "passive"))
      (node (ref "U4") (pin "5") (pinfunction "ILIM_5") (pintype "passive"))
    )
    (net (code "37") (name "/IO8") (class "Default")
      (node (ref "BOARD1") (pin "D8") (pinfunction "D8_D8") (pintype "bidirectional"))
      (node (ref "M1") (pin "35") (pinfunction "IO8_35") (pintype "bidirectional"))
    )
    (net (code "38") (name "/IO9") (class "Default")
      (node (ref "BOARD1") (pin "D9") (pinfunction "D9_D9") (pintype "bidirectional"))
      (node (ref "M1") (pin "36") (pinfunction "IO9_36") (pintype "bidirectional"))
    )
    (net (code "39") (name "/IO10") (class "Default")
      (node (ref "BOARD1") (pin "D10") (pinfunction "D10_D10") (pintype "bidirectional"))
      (node (ref "M1") (pin "37") (pinfunction "IO10_37") (pintype "bidirectional"))
    )
    (net (code "40") (name "/IO11") (class "Default")
      (node (ref "BOARD1") (pin "D11") (pinfunction "D11_D11") (pintype "bidirectional"))
      (node (ref "M1") (pin "38") (pinfunction "IO11_38") (pintype "bidirectional"))
    )
    (net (code "41") (name "/IO12") (class "Default")
      (node (ref "BOARD1") (pin "D12") (pinfunction "D12_D12") (pintype "bidirectional"))
      (node (ref "M1") (pin "39") (pinfunction "IO12_39") (pintype "bidirectional"))
    )
    (net (code "42") (name "/IO13") (class "Default")
      (node (ref "BOARD1") (pin "D13") (pinfunction "D13_D13") (pintype "bidirectional"))
      (node (ref "M1") (pin "41") (pinfunction "IO13_41") (pintype "bidirectional"))
    )
    (net (code "43") (name "/MISO") (class "Default")
      (node (ref "BOARD1") (pin "1") (pinfunction "MISO_1") (pintype "input"))
      (node (ref "M1") (pin "17") (pinfunction "MISO_17") (pintype "bidirectional"))
    )
    (net (code "44") (name "/MOSI") (class "Default")
      (node (ref "BOARD1") (pin "4") (pinfunction "MOSI_4") (pintype "output"))
      (node (ref "M1") (pin "15") (pinfunction "MOSI_15") (pintype "bidirectional"))
    )
    (net (code "45") (name "/P4_RX") (class "Default")
      (node (ref "C5") (pin "2") (pinfunction "2_2") (pintype "passive"))
      (node (ref "R1") (pin "1") (pinfunction "1_1") (pintype "passive"))
      (node (ref "R3") (pin "1") (pinfunction "1_1") (pintype "passive"))
    )
    (net (code "46") (name "/P4_RX_N") (class "Default")
      (node (ref "J8") (pin "6") (pinfunction "P6_6") (pintype "passive"))
      (node (ref "M1") (pin "5") (pinfunction "P4_RX-_5") (pintype "bidirectional"))
      (node (ref "R1") (pin "2") (pinfunction "2_2") (pintype "passive"))
    )
    (net (code "47") (name "/P4_RX_P") (class "Default")
      (node (ref "J8") (pin "3") (pinfunction "P3_3") (pintype "passive"))
      (node (ref "M1") (pin "4") (pinfunction "P4_RX+_4") (pintype "bidirectional"))
      (node (ref "R3") (pin "2") (pinfunction "2_2") (pintype "passive"))
    )
    (net (code "48") (name "/P4_TX") (class "Default")
      (node (ref "C2") (pin "2") (pinfunction "2_2") (pintype "passive"))
      (node (ref "R2") (pin "1") (pinfunction "1_1") (pintype "passive"))
      (node (ref "R8") (pin "1") (pinfunction "1_1") (pintype "passive"))
    )
    (net (code "49") (name "/P4_TX_N") (class "Default")
      (node (ref "J8") (pin "2") (pinfunction "P2_2") (pintype "passive"))
      (node (ref "M1") (pin "7") (pinfunction "P4_TX-_7") (pintype "bidirectional"))
      (node (ref "R8") (pin "2") (pinfunction "2_2") (pintype "passive"))
    )
    (net (code "50") (name "/P4_TX_P") (class "Default")
      (node (ref "J8") (pin "1") (pinfunction "P1_1") (pintype "passive"))
      (node (ref "M1") (pin "6") (pinfunction "P4_TX+_6") (pintype "bidirectional"))
      (node (ref "R2") (pin "2") (pinfunction "2_2") (pintype "passive"))
    )
    (net (code "51") (name "/RXD1") (class "Default")
      (node (ref "BOARD1") (pin "D0") (pinfunction "D0(RX0)_D0") (pintype "bidirectional"))
      (node (ref "M1") (pin "24") (pinfunction "RXD1_24") (pintype "bidirectional"))
    )
    (net (code "52") (name "/SCK") (class "Default")
      (node (ref "BOARD1") (pin "3") (pinfunction "SCK_3") (pintype "output"))
      (node (ref "M1") (pin "14") (pinfunction "SCK_14") (pintype "bidirectional"))
    )
    (net (code "53") (name "/SCL") (class "Default")
      (node (ref "BOARD1") (pin "D3") (pinfunction "D3_D3") (pintype "bidirectional"))
      (node (ref "BOARD1") (pin "SCL") (pinfunction "SCL_SCL") (pintype "bidirectional"))
      (node (ref "M1") (pin "28") (pinfunction "SCL_28") (pintype "bidirectional"))
    )
    (net (code "54") (name "/SDA") (class "Default")
      (node (ref "BOARD1") (pin "D2") (pinfunction "D2_D2") (pintype "bidirectional"))
      (node (ref "BOARD1") (pin "SDA") (pinfunction "SDA_SDA") (pintype "bidirectional"))
      (node (ref "M1") (pin "26") (pinfunction "SDA_26") (pintype "bidirectional"))
    )
    (net (code "55") (name "/SDCLK") (class "Default")
      (node (ref "C25") (pin "1") (pinfunction "1_1") (pintype "passive"))
      (node (ref "D7") (pin "4") (pinfunction "I/O3_4") (pintype "passive"))
      (node (ref "R30") (pin "1") (pinfunction "1_1") (pintype "passive"))
      (node (ref "S4") (pin "5") (pinfunction "CLK_5") (pintype "input"))
    )
    (net (code "56") (name "/SDCMD") (class "Default")
      (node (ref "D7") (pin "6") (pinfunction "I/O4_6") (pintype "passive"))
      (node (ref "R26") (pin "1") (pinfunction "1_1") (pintype "passive"))
      (node (ref "S4") (pin "3") (pinfunction "CMD_3") (pintype "input"))
      (node (ref "U3") (pin "27") (pinfunction "CARDDATA0_27") (pintype "bidirectional"))
    )
    (net (code "57") (name "/SDDAT0") (class "Default")
      (node (ref "D8") (pin "3") (pinfunction "I/O2_3") (pintype "passive"))
      (node (ref "S4") (pin "7") (pinfunction "DAT0_7") (pintype "bidirectional"))
      (node (ref "U3") (pin "31") (pinfunction "CARDDATA4_31") (pintype "bidirectional"))
    )
    (net (code "58") (name "/SDDAT1") (class "Default")
      (node (ref "D8") (pin "1") (pinfunction "I/O1_1") (pintype "passive"))
      (node (ref "S4") (pin "8") (pinfunction "DAT1_8") (pintype "bidirectional"))
      (node (ref "U3") (pin "32") (pinfunction "CARDDATA5_32") (pintype "bidirectional"))
    )
    (net (code "59") (name "/SDDAT3") (class "Default")
      (node (ref "D7") (pin "3") (pinfunction "I/O2_3") (pintype "passive"))
      (node (ref "S4") (pin "2") (pinfunction "CD/DAT3_2") (pintype "bidirectional"))
      (node (ref "U3") (pin "34") (pinfunction "CARDDATA7_34") (pintype "bidirectional"))
    )
    (net (code "60") (name "/SDDDAT2") (class "Default")
      (node (ref "D7") (pin "1") (pinfunction "I/O1_1") (pintype "passive"))
      (node (ref "S4") (pin "1") (pinfunction "DAT2_1") (pintype "bidirectional"))
      (node (ref "U3") (pin "33") (pinfunction "CARDDATA6_33") (pintype "bidirectional"))
    )
    (net (code "61") (name "/SDVDD") (class "Default")
      (node (ref "C8") (pin "1") (pinfunction "1_1") (pintype "passive"))
      (node (ref "D7") (pin "5") (pinfunction "VCC_5") (pintype "passive"))
      (node (ref "D8") (pin "5") (pinfunction "VCC_5") (pintype "passive"))
      (node (ref "R25") (pin "2") (pinfunction "2_2") (pintype "passive"))
      (node (ref "R26") (pin "2") (pinfunction "2_2") (pintype "passive"))
      (node (ref "S4") (pin "4") (pinfunction "VDD_4") (pintype "power_in"))
    )
    (net (code "62") (name "/SDWP") (class "Default")
      (node (ref "R28") (pin "2") (pinfunction "2_2") (pintype "passive"))
      (node (ref "U3") (pin "29") (pinfunction "CARDDATA2_29") (pintype "bidirectional"))
    )
    (net (code "63") (name "/SD_V33") (class "Default")
      (node (ref "R25") (pin "1") (pinfunction "1_1") (pintype "passive"))
      (node (ref "U3") (pin "12") (pinfunction "SD_V33_12") (pintype "power_in"))
    )
    (net (code "64") (name "/SS") (class "Default")
      (node (ref "M1") (pin "16") (pinfunction "SS_16") (pintype "bidirectional"))
    )
    (net (code "65") (name "/TXD1") (class "Default")
      (node (ref "BOARD1") (pin "D1") (pinfunction "D1(TX0)_D1") (pintype "bidirectional"))
      (node (ref "M1") (pin "25") (pinfunction "TXD1_25") (pintype "bidirectional"))
    )
    (net (code "66") (name "/UP_N") (class "Default")
      (node (ref "J2") (pin "2") (pinfunction "2_2") (pintype "passive"))
      (node (ref "R40") (pin "2") (pinfunction "2_2") (pintype "passive"))
    )
    (net (code "67") (name "/UP_P") (class "Default")
      (node (ref "J2") (pin "3") (pinfunction "3_3") (pintype "passive"))
      (node (ref "R39") (pin "2") (pinfunction "2_2") (pintype "passive"))
    )
    (net (code "68") (name "/USB1_N") (class "Default")
      (node (ref "R5") (pin "2") (pinfunction "2_2") (pintype "passive"))
      (node (ref "U3") (pin "44") (pinfunction "USB1_DM_44") (pintype "passive"))
    )
    (net (code "69") (name "/USB1_P") (class "Default")
      (node (ref "R6") (pin "2") (pinfunction "2_2") (pintype "passive"))
      (node (ref "U3") (pin "45") (pinfunction "USB1_DP_45") (pintype "passive"))
    )
    (net (code "70") (name "/USB2_N") (class "Default")
      (node (ref "R29") (pin "2") (pinfunction "2_2") (pintype "passive"))
      (node (ref "U3") (pin "4") (pinfunction "DP2_DM_4") (pintype "passive"))
    )
    (net (code "71") (name "/USB2_P") (class "Default")
      (node (ref "R31") (pin "2") (pinfunction "2_2") (pintype "passive"))
      (node (ref "U3") (pin "5") (pinfunction "DP2_DP_5") (pintype "passive"))
    )
    (net (code "72") (name "/USB3_N") (class "Default")
      (node (ref "R32") (pin "2") (pinfunction "2_2") (pintype "passive"))
      (node (ref "U3") (pin "7") (pinfunction "DP3_DM_7") (pintype "passive"))
    )
    (net (code "73") (name "/USB3_P") (class "Default")
      (node (ref "R33") (pin "2") (pinfunction "2_2") (pintype "passive"))
      (node (ref "U3") (pin "8") (pinfunction "DP3_DP_8") (pintype "passive"))
    )
    (net (code "74") (name "/USB_N") (class "Default")
      (node (ref "M1") (pin "20") (pinfunction "USB_N_20") (pintype "bidirectional"))
      (node (ref "R16") (pin "1") (pinfunction "1_1") (pintype "passive"))
      (node (ref "R40") (pin "1") (pinfunction "1_1") (pintype "passive"))
      (node (ref "U3") (pin "41") (pinfunction "USB_DM_41") (pintype "passive"))
    )
    (net (code "75") (name "/USB_P") (class "Default")
      (node (ref "M1") (pin "21") (pinfunction "USB_P_21") (pintype "bidirectional"))
      (node (ref "R17") (pin "1") (pinfunction "1_1") (pintype "passive"))
      (node (ref "R39") (pin "1") (pinfunction "1_1") (pintype "passive"))
      (node (ref "U3") (pin "42") (pinfunction "USB_DP_42") (pintype "passive"))
    )
    (net (code "76") (name "/VIN") (class "Default")
      (node (ref "BOARD1") (pin "VIN") (pinfunction "VIN_VIN") (pintype "power_in"))
      (node (ref "M1") (pin "40") (pinfunction "VIN_40") (pintype "power_in"))
    )
    (net (code "77") (name "/VUSB") (class "Default")
      (node (ref "J2") (pin "1") (pinfunction "1_1") (pintype "passive"))
      (node (ref "L1") (pin "1") (pinfunction "1_1") (pintype "passive"))
    )
    (net (code "78") (name "/~{RESET}") (class "Default")
      (node (ref "BOARD1") (pin "5") (pinfunction "RESET_5") (pintype "input"))
      (node (ref "BOARD1") (pin "RESET$1") (pinfunction "RESET_RESET$1") (pintype "bidirectional"))
      (node (ref "M1") (pin "27") (pinfunction "~{RESET}_27") (pintype "input"))
    )
    (net (code "79") (name "/~{SDCD}") (class "Default")
      (node (ref "D8") (pin "6") (pinfunction "I/O4_6") (pintype "passive"))
      (node (ref "R27") (pin "2") (pinfunction "2_2") (pintype "passive"))
      (node (ref "S4") (pin "CD") (pinfunction "S+_CD") (pintype "output"))
      (node (ref "U3") (pin "23") (pinfunction "SDCDN_23") (pintype "input"))
    )
    (net (code "80") (name "GND") (class "Default")
      (node (ref "BOARD1") (pin "6") (pinfunction "GND_6") (pintype "power_in"))
      (node (ref "BOARD1") (pin "GND$1") (pinfunction "GND_GND$1") (pintype "power_in"))
      (node (ref "BOARD1") (pin "GND$2") (pinfunction "GND_GND$2") (pintype "power_in"))
      (node (ref "BOARD1") (pin "GND$3") (pinfunction "GND_GND$3") (pintype "power_in"))
      (node (ref "C1") (pin "1") (pinfunction "1_1") (pintype "passive"))
      (node (ref "C10") (pin "1") (pinfunction "1_1") (pintype "passive"))
      (node (ref "C11") (pin "2") (pinfunction "2_2") (pintype "passive"))
      (node (ref "C12") (pin "1") (pinfunction "1_1") (pintype "passive"))
      (node (ref "C13") (pin "1") (pinfunction "1_1") (pintype "passive"))
      (node (ref "C14") (pin "2") (pinfunction "2_2") (pintype "passive"))
      (node (ref "C18") (pin "1") (pinfunction "1_1") (pintype "passive"))
      (node (ref "C2") (pin "1") (pinfunction "1_1") (pintype "passive"))
      (node (ref "C22") (pin "1") (pinfunction "1_1") (pintype "passive"))
      (node (ref "C23") (pin "1") (pinfunction "1_1") (pintype "passive"))
      (node (ref "C24") (pin "2") (pinfunction "2_2") (pintype "passive"))
      (node (ref "C25") (pin "2") (pinfunction "2_2") (pintype "passive"))
      (node (ref "C26") (pin "2") (pinfunction "2_2") (pintype "passive"))
      (node (ref "C27") (pin "2") (pinfunction "-_2") (pintype "passive"))
      (node (ref "C28") (pin "2") (pinfunction "2_2") (pintype "passive"))
      (node (ref "C29") (pin "2") (pinfunction "2_2") (pintype "passive"))
      (node (ref "C3") (pin "1") (pinfunction "1_1") (pintype "passive"))
      (node (ref "C30") (pin "2") (pinfunction "2_2") (pintype "passive"))
      (node (ref "C4") (pin "1") (pinfunction "1_1") (pintype "passive"))
      (node (ref "C5") (pin "1") (pinfunction "1_1") (pintype "passive"))
      (node (ref "C6") (pin "1") (pinfunction "1_1") (pintype "passive"))
      (node (ref "C7") (pin "1") (pinfunction "1_1") (pintype "passive"))
      (node (ref "C8") (pin "2") (pinfunction "2_2") (pintype "passive"))
      (node (ref "C9") (pin "2") (pinfunction "2_2") (pintype "passive"))
      (node (ref "D2") (pin "1") (pinfunction "P$1_1") (pintype "passive"))
      (node (ref "D5") (pin "1") (pinfunction "P$1_1") (pintype "passive"))
      (node (ref "D6") (pin "1") (pinfunction "P$1_1") (pintype "passive"))
      (node (ref "D7") (pin "2") (pinfunction "GND_2") (pintype "passive"))
      (node (ref "D8") (pin "2") (pinfunction "GND_2") (pintype "passive"))
      (node (ref "J1") (pin "7") (pinfunction "7_7") (pintype "passive"))
      (node (ref "J1") (pin "8") (pinfunction "8_8") (pintype "passive"))
      (node (ref "L3") (pin "1") (pinfunction "1_1") (pintype "passive"))
      (node (ref "M1") (pin "18") (pinfunction "GND_18") (pintype "power_in"))
      (node (ref "M1") (pin "22") (pinfunction "GND_22") (pintype "power_in"))
      (node (ref "M1") (pin "23") (pinfunction "GND_23") (pintype "power_in"))
      (node (ref "M1") (pin "3") (pinfunction "GND_3") (pintype "power_in"))
      (node (ref "M1") (pin "33") (pinfunction "GND_33") (pintype "power_in"))
      (node (ref "M1") (pin "44") (pinfunction "GND_44") (pintype "power_in"))
      (node (ref "R16") (pin "2") (pinfunction "2_2") (pintype "passive"))
      (node (ref "R17") (pin "2") (pinfunction "2_2") (pintype "passive"))
      (node (ref "R24") (pin "1") (pinfunction "1_1") (pintype "passive"))
      (node (ref "R27") (pin "1") (pinfunction "1_1") (pintype "passive"))
      (node (ref "R28") (pin "1") (pinfunction "1_1") (pintype "passive"))
      (node (ref "R35") (pin "2") (pinfunction "2_2") (pintype "passive"))
      (node (ref "R4") (pin "2") (pinfunction "2_2") (pintype "passive"))
      (node (ref "S4") (pin "6") (pinfunction "VSS_6") (pintype "power_in"))
      (node (ref "S4") (pin "G$1") (pinfunction "G_G$1") (pintype "power_in"))
      (node (ref "S4") (pin "G$2") (pinfunction "G_G$2") (pintype "power_in"))
      (node (ref "S4") (pin "G$3") (pinfunction "G_G$3") (pintype "power_in"))
      (node (ref "S4") (pin "S-/G") (pinfunction "S-_S-/G") (pintype "power_in"))
      (node (ref "S5") (pin "4") (pinfunction "4_4") (pintype "passive"))
      (node (ref "S5") (pin "G$1") (pinfunction "G_G$1") (pintype "passive"))
      (node (ref "S5") (pin "G$2") (pinfunction "G_G$2") (pintype "passive"))
      (node (ref "S5") (pin "G$3") (pinfunction "G_G$3") (pintype "passive"))
      (node (ref "S5") (pin "G$4") (pinfunction "G_G$4") (pintype "passive"))
      (node (ref "U3") (pin "15") (pinfunction "PLL_VSS_15") (pintype "power_in"))
      (node (ref "U3") (pin "3") (pinfunction "PVSS_3") (pintype "power_in"))
      (node (ref "U3") (pin "40") (pinfunction "VSSH_40") (pintype "power_in"))
      (node (ref "U4") (pin "2") (pinfunction "GND_2") (pintype "power_in"))
      (node (ref "Y1") (pin "2") (pinfunction "2_2") (pintype "passive"))
      (node (ref "Y1") (pin "4") (pinfunction "4_4") (pintype "passive"))
    )
    (net (code "81") (name "Net-(U3-AVDD5V)") (class "Default")
      (node (ref "C11") (pin "1") (pinfunction "1_1") (pintype "passive"))
      (node (ref "R7") (pin "1") (pinfunction "1_1") (pintype "passive"))
      (node (ref "U3") (pin "11") (pinfunction "AVDD5V_11") (pintype "power_in"))
    )
    (net (code "82") (name "Net-(U3-BUS_PWREDN)") (class "Default")
      (node (ref "R18") (pin "2") (pinfunction "2_2") (pintype "passive"))
      (node (ref "U3") (pin "17") (pinfunction "BUS_PWREDN_17") (pintype "input"))
    )
    (net (code "83") (name "Net-(U3-MSINS)") (class "Default")
      (node (ref "R22") (pin "2") (pinfunction "2_2") (pintype "passive"))
      (node (ref "U3") (pin "22") (pinfunction "MSINS_22") (pintype "input"))
    )
    (net (code "84") (name "Net-(U3-PLL_VDD)") (class "Default")
      (node (ref "C12") (pin "2") (pinfunction "2_2") (pintype "passive"))
      (node (ref "C14") (pin "1") (pinfunction "1_1") (pintype "passive"))
      (node (ref "C23") (pin "2") (pinfunction "2_2") (pintype "passive"))
      (node (ref "U3") (pin "13") (pinfunction "V18_13") (pintype "power_in"))
      (node (ref "U3") (pin "14") (pinfunction "PLL_VDD_14") (pintype "power_in"))
      (node (ref "U3") (pin "18") (pinfunction "VDD_18") (pintype "power_in"))
      (node (ref "U3") (pin "26") (pinfunction "VDD_26") (pintype "power_in"))
    )
    (net (code "85") (name "Net-(U3-UP_RREF)") (class "Default")
      (node (ref "R4") (pin "1") (pinfunction "1_1") (pintype "passive"))
      (node (ref "U3") (pin "47") (pinfunction "UP_RREF_47") (pintype "passive"))
    )
    (net (code "86") (name "Net-(U3-V33)") (class "Default")
      (node (ref "R19") (pin "1") (pinfunction "1_1") (pintype "passive"))
      (node (ref "U3") (pin "10") (pinfunction "V33_10") (pintype "power_in"))
    )
    (net (code "87") (name "Net-(U3-XSCI)") (class "Default")
      (node (ref "C6") (pin "2") (pinfunction "2_2") (pintype "passive"))
      (node (ref "U3") (pin "2") (pinfunction "XSCI_2") (pintype "passive"))
      (node (ref "Y1") (pin "3") (pinfunction "3_3") (pintype "passive"))
    )
    (net (code "88") (name "Net-(U3-XSCO)") (class "Default")
      (node (ref "C4") (pin "2") (pinfunction "2_2") (pintype "passive"))
      (node (ref "U3") (pin "1") (pinfunction "XSCO_1") (pintype "passive"))
      (node (ref "Y1") (pin "1") (pinfunction "1_1") (pintype "passive"))
    )
    (net (code "89") (name "Net-(U3-~{CHIPRESET})") (class "Default")
      (node (ref "R21") (pin "2") (pinfunction "2_2") (pintype "passive"))
      (node (ref "U3") (pin "21") (pinfunction "~{CHIPRESET}_21") (pintype "input"))
    )
    (net (code "90") (name "SHIELD") (class "Default")
      (node (ref "C13") (pin "2") (pinfunction "2_2") (pintype "passive"))
      (node (ref "C3") (pin "2") (pinfunction "2_2") (pintype "passive"))
      (node (ref "J8") (pin "8") (pinfunction "P8_8") (pintype "power_in"))
      (node (ref "J8") (pin "SH$1") (pinfunction "SHIELD_SH$1") (pintype "power_in"))
      (node (ref "J8") (pin "SH$2") (pinfunction "SHIELD_SH$2") (pintype "power_in"))
    )
    (net (code "91") (name "unconnected-(BOARD1-PadNC)") (class "Default")
      (node (ref "BOARD1") (pin "NC") (pinfunction "NC_NC") (pintype "no_connect"))
    )
    (net (code "92") (name "unconnected-(D8-I{slash}O3-Pad4)") (class "Default")
      (node (ref "D8") (pin "4") (pinfunction "I/O3_4") (pintype "passive"))
    )
    (net (code "93") (name "unconnected-(J1-Pad9)") (class "Default")
      (node (ref "J1") (pin "9") (pinfunction "9_9") (pintype "passive"))
    )
    (net (code "94") (name "unconnected-(J1-Pad10)") (class "Default")
      (node (ref "J1") (pin "10") (pinfunction "10_10") (pintype "passive"))
    )
    (net (code "95") (name "unconnected-(J8-P7-Pad7)") (class "Default")
      (node (ref "J8") (pin "7") (pinfunction "P7_7") (pintype "no_connect"))
    )
    (net (code "96") (name "unconnected-(U3-CARDDATA1-Pad28)") (class "Default")
      (node (ref "U3") (pin "28") (pinfunction "CARDDATA1_28") (pintype "bidirectional"))
    )
    (net (code "97") (name "unconnected-(U3-CARDDATA3-Pad30)") (class "Default")
      (node (ref "U3") (pin "30") (pinfunction "CARDDATA3_30") (pintype "bidirectional"))
    )
    (net (code "98") (name "unconnected-(U3-CARDDATA8-Pad35)") (class "Default")
      (node (ref "U3") (pin "35") (pinfunction "CARDDATA8_35") (pintype "bidirectional"))
    )
    (net (code "99") (name "unconnected-(U3-CARDDATA9-Pad36)") (class "Default")
      (node (ref "U3") (pin "36") (pinfunction "CARDDATA9_36") (pintype "bidirectional"))
    )
    (net (code "100") (name "unconnected-(U3-CARDDATA10-Pad37)") (class "Default")
      (node (ref "U3") (pin "37") (pinfunction "CARDDATA10_37") (pintype "bidirectional"))
    )
    (net (code "101") (name "unconnected-(U3-CARDDATA11-Pad38)") (class "Default")
      (node (ref "U3") (pin "38") (pinfunction "CARDDATA11_38") (pintype "bidirectional"))
    )
    (net (code "102") (name "unconnected-(U3-CONTROLOUT1-Pad24)") (class "Default")
      (node (ref "U3") (pin "24") (pinfunction "CONTROLOUT1_24") (pintype "output"))
    )
  )
)
